# Alimentation.net
KiCad netlist of a schematic drawn in Altium Designer
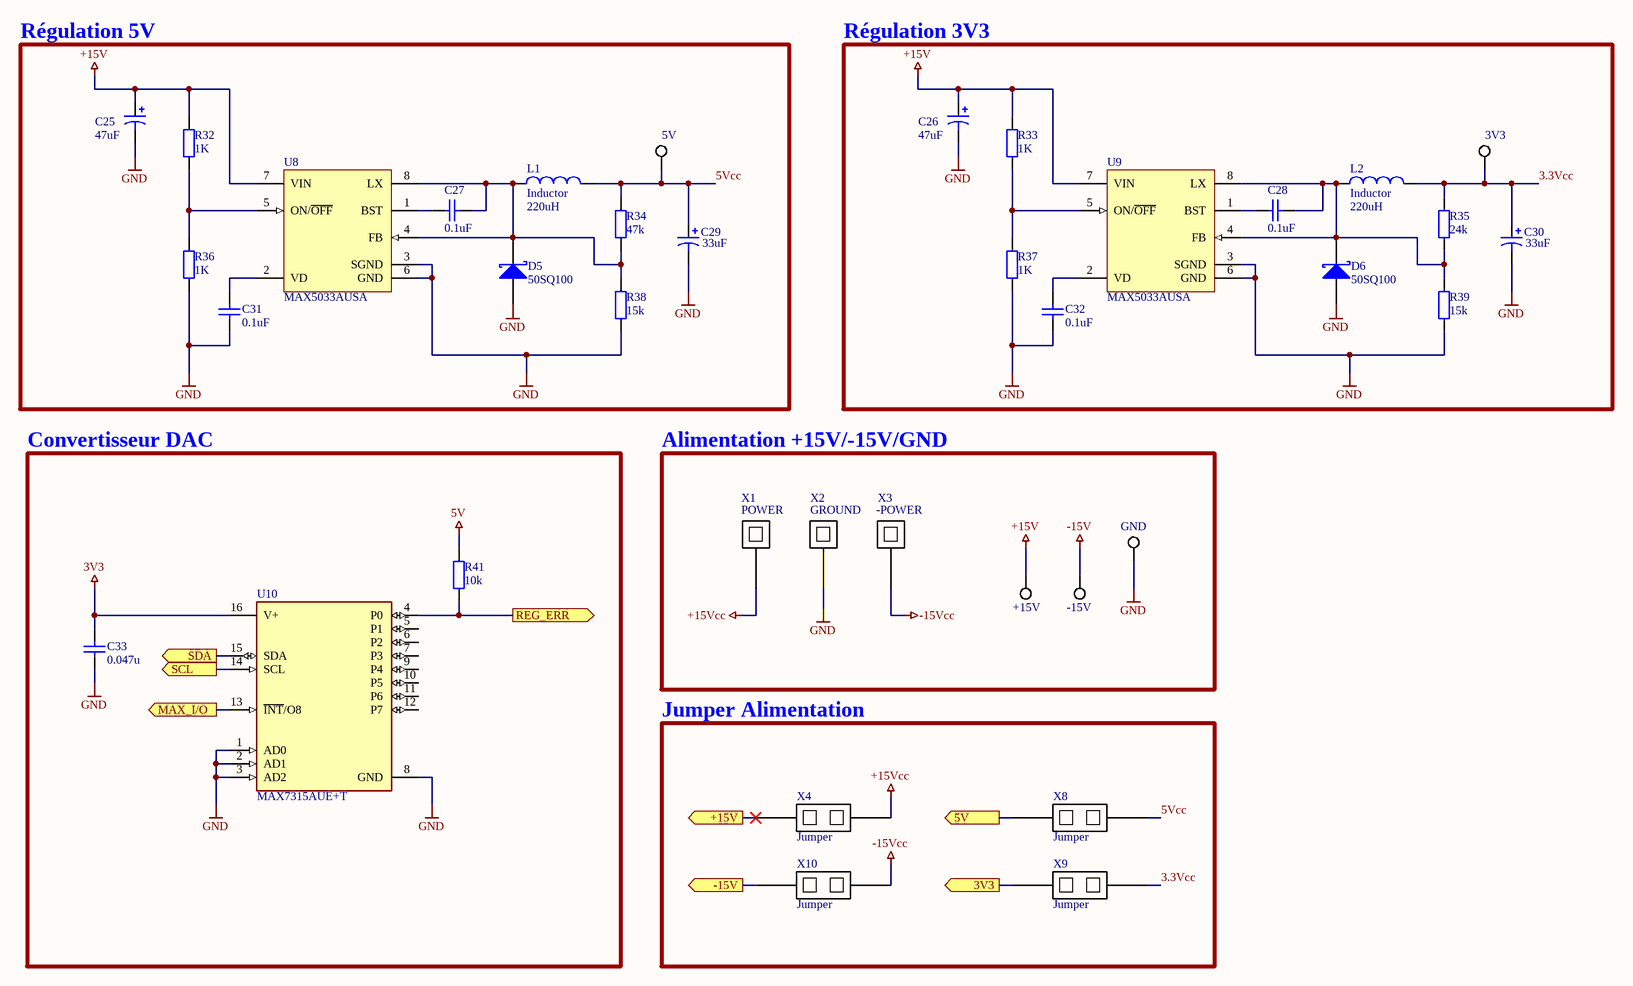
[diagram p0: Alimentation.SchDoc]

(export (version "E")
  (design (tool "Eeschema 10.0.6"))
  (components
    (comp (ref "+15V")
      (value "REGP")
      (footprint "KSTN-5019_V")
      (description "Test Point, 1 Position SMD, RoHS, Tape and Reel")
      (libsource (lib "Altium Content Vault") (part "TESTPOINT_WHITE"))
    )
    (comp (ref "-15V")
      (value "REGP")
      (footprint "KSTN-5019_V")
      (description "Test Point, 1 Position SMD, RoHS, Tape and Reel")
      (libsource (lib "Altium Content Vault") (part "TESTPOINT_WHITE"))
    )
    (comp (ref "3V3")
      (value "REGP")
      (footprint "KSTN-5019_V")
      (description "Test Point, 1 Position SMD, RoHS, Tape and Reel")
      (libsource (lib "Altium Content Vault") (part "TESTPOINT_WHITE"))
    )
    (comp (ref "5V")
      (value "REGP")
      (footprint "KSTN-5019_V")
      (description "Test Point, 1 Position SMD, RoHS, Tape and Reel")
      (libsource (lib "Altium Content Vault") (part "TESTPOINT_WHITE"))
    )
    (comp (ref "C25")
      (value "47uF")
      (footprint "C0805")
      (description "Cap Pol 47uF")
      (fields (field (name "Comment") "Cap Pol1") (field (name "PUBLISHER") "Altium Limited"))
      (libsource (lib "Miscellaneous Devices") (part "Cap Pol1"))
    )
    (comp (ref "C26")
      (value "47uF")
      (footprint "C0805")
      (description "Cap Pol 47uF")
      (fields (field (name "Comment") "Cap Pol1") (field (name "PUBLISHER") "Altium Limited"))
      (libsource (lib "Miscellaneous Devices") (part "Cap Pol1"))
    )
    (comp (ref "C27")
      (value "0.1uF")
      (footprint "C0805")
      (description "Cap 100nF")
      (fields (field (name "Comment") "Cap") (field (name "PUBLISHER") "Altium Limited"))
      (libsource (lib "Miscellaneous Devices") (part "Cap"))
    )
    (comp (ref "C28")
      (value "0.1uF")
      (footprint "C0805")
      (description "Cap 100nF")
      (fields (field (name "Comment") "Cap") (field (name "PUBLISHER") "Altium Limited"))
      (libsource (lib "Miscellaneous Devices") (part "Cap"))
    )
    (comp (ref "C29")
      (value "33uF")
      (footprint "C0805")
      (description "Cap Pol 33uF")
      (fields (field (name "Comment") "Cap Pol1") (field (name "PUBLISHER") "Altium Limited"))
      (libsource (lib "Miscellaneous Devices") (part "Cap Pol1"))
    )
    (comp (ref "C30")
      (value "33uF")
      (footprint "C0805")
      (description "Cap Pol 33uF")
      (fields (field (name "Comment") "Cap Pol1") (field (name "PUBLISHER") "Altium Limited"))
      (libsource (lib "Miscellaneous Devices") (part "Cap Pol1"))
    )
    (comp (ref "C31")
      (value "0.1uF")
      (footprint "C0805")
      (description "Cap 100nF")
      (fields (field (name "Comment") "Cap") (field (name "PUBLISHER") "Altium Limited"))
      (libsource (lib "Miscellaneous Devices") (part "Cap"))
    )
    (comp (ref "C32")
      (value "0.1uF")
      (footprint "C0805")
      (description "Cap 100nF")
      (fields (field (name "Comment") "Cap") (field (name "PUBLISHER") "Altium Limited"))
      (libsource (lib "Miscellaneous Devices") (part "Cap"))
    )
    (comp (ref "C33")
      (value "0.047u")
      (footprint "C0805")
      (description "Cap 0.047uF")
      (fields (field (name "Comment") "Cap") (field (name "PUBLISHER") "Altium Limited"))
      (libsource (lib "Miscellaneous Devices") (part "Cap"))
    )
    (comp (ref "D5")
      (value "50SQ100")
      (footprint "SODFL2513X70N")
      (description "Schottky Diode 50SQ100")
      (fields (field (name "PUBLISHER") "Altium Limited"))
      (libsource (lib "Miscellaneous Devices") (part "D Schottky"))
    )
    (comp (ref "D6")
      (value "50SQ100")
      (footprint "SODFL2513X70N")
      (description "Schottky Diode 50SQ100")
      (fields (field (name "PUBLISHER") "Altium Limited"))
      (libsource (lib "Miscellaneous Devices") (part "D Schottky"))
    )
    (comp (ref "GND")
      (value "REGP")
      (footprint "KSTN-5019_V")
      (description "Test Point, 1 Position SMD, RoHS, Tape and Reel")
      (libsource (lib "Altium Content Vault") (part "TESTPOINT_WHITE"))
    )
    (comp (ref "L1")
      (value "Inductor")
      (footprint "SDE0604A101K")
      (description "Inductor 220uH")
      (fields (field (name "ALTIUM_VALUE") "220uH") (field (name "PUBLISHER") "Altium Limited"))
      (libsource (lib "Miscellaneous Devices") (part "Inductor"))
    )
    (comp (ref "L2")
      (value "Inductor")
      (footprint "SDE0604A101K")
      (description "Inductor 220uH")
      (fields (field (name "ALTIUM_VALUE") "220uH") (field (name "PUBLISHER") "Altium Limited"))
      (libsource (lib "Miscellaneous Devices") (part "Inductor"))
    )
    (comp (ref "R32")
      (value "1K")
      (footprint "6-0805_N")
      (description "Res 1K")
      (fields (field (name "Comment") "Res2") (field (name "PUBLISHER") "Altium Limited"))
      (libsource (lib "Miscellaneous Devices") (part "Res2"))
    )
    (comp (ref "R33")
      (value "1K")
      (footprint "6-0805_N")
      (description "Res 1K")
      (fields (field (name "PUBLISHER") "Altium Limited"))
      (libsource (lib "Miscellaneous Devices") (part "Res2"))
    )
    (comp (ref "R34")
      (value "47k")
      (footprint "6-0805_N")
      (description "Resistor")
      (fields (field (name "Comment") "Res2") (field (name "PUBLISHER") "Altium Limited"))
      (libsource (lib "Miscellaneous Devices") (part "Res2"))
    )
    (comp (ref "R35")
      (value "24k")
      (footprint "6-0805_N")
      (description "Res 24K")
      (fields (field (name "Comment") "Res2") (field (name "PUBLISHER") "Altium Limited"))
      (libsource (lib "Miscellaneous Devices") (part "Res2"))
    )
    (comp (ref "R36")
      (value "1K")
      (footprint "6-0805_N")
      (description "Res 1K")
      (fields (field (name "Comment") "Res2") (field (name "PUBLISHER") "Altium Limited"))
      (libsource (lib "Miscellaneous Devices") (part "Res2"))
    )
    (comp (ref "R37")
      (value "1K")
      (footprint "6-0805_N")
      (description "Res 1K")
      (fields (field (name "PUBLISHER") "Altium Limited"))
      (libsource (lib "Miscellaneous Devices") (part "Res2"))
    )
    (comp (ref "R38")
      (value "15k")
      (footprint "6-0805_N")
      (description "Resistor")
      (fields (field (name "Comment") "Res2") (field (name "PUBLISHER") "Altium Limited"))
      (libsource (lib "Miscellaneous Devices") (part "Res2"))
    )
    (comp (ref "R39")
      (value "15k")
      (footprint "6-0805_N")
      (description "Res 15K")
      (fields (field (name "Comment") "Res2") (field (name "PUBLISHER") "Altium Limited"))
      (libsource (lib "Miscellaneous Devices") (part "Res2"))
    )
    (comp (ref "R41")
      (value "10k")
      (footprint "6-0805_N")
      (description "Res 10K")
      (fields (field (name "Comment") "Res2") (field (name "PUBLISHER") "Altium Limited"))
      (libsource (lib "Miscellaneous Devices") (part "Res2"))
    )
    (comp (ref "U8")
      (value "MAX5033AUSA")
      (footprint "S8-5_N")
      (libsource (lib "Altium Content Vault") (part "MAX-MAX5033-IL8"))
    )
    (comp (ref "U9")
      (value "MAX5033AUSA")
      (footprint "S8-5_N")
      (libsource (lib "Altium Content Vault") (part "MAX-MAX5033-IL8"))
    )
    (comp (ref "U10")
      (value "MAX7315AUE+T")
      (footprint "FP-U16-2-MFG")
      (description "IC I/O EXPANDER I2C 8B 16TSSOP")
      (libsource (lib "Altium Content Vault") (part "92d7aca338a602ce8c8694935fca5a5"))
    )
    (comp (ref "X1")
      (value "POWER")
      (footprint "PIN1")
      (description "CONN HEADER VERT 1POS")
      (libsource (lib "2019_RegThermiqueMyRio") (part "Berg"))
    )
    (comp (ref "X2")
      (value "GROUND")
      (footprint "PIN1")
      (description "CONN HEADER VERT 1POS")
      (libsource (lib "2019_RegThermiqueMyRio") (part "Berg"))
    )
    (comp (ref "X3")
      (value "-POWER")
      (footprint "PIN1")
      (description "CONN HEADER VERT 1POS")
      (libsource (lib "2019_RegThermiqueMyRio") (part "Berg"))
    )
    (comp (ref "X4")
      (value "Jumper")
      (footprint "HDR1X2")
      (description "CONN HEADER VERT 2POS 2.54MM")
      (libsource (lib "2019_RegThermiqueMyRio") (part "Jumper"))
    )
    (comp (ref "X8")
      (value "Jumper")
      (footprint "HDR1X2")
      (description "CONN HEADER VERT 2POS 2.54MM")
      (libsource (lib "2019_RegThermiqueMyRio") (part "Jumper"))
    )
    (comp (ref "X9")
      (value "Jumper")
      (footprint "HDR1X2")
      (description "CONN HEADER VERT 2POS 2.54MM")
      (libsource (lib "2019_RegThermiqueMyRio") (part "Jumper"))
    )
    (comp (ref "X10")
      (value "Jumper")
      (footprint "HDR1X2")
      (description "CONN HEADER VERT 2POS 2.54MM")
      (libsource (lib "2019_RegThermiqueMyRio") (part "Jumper"))
    )
  )
  (nets
    (net (code "1") (name "+15V") (class "Default")
      (node (ref "+15V") (pin "1") (pinfunction "1_1") (pintype "passive"))
      (node (ref "C25") (pin "1") (pinfunction "1_1") (pintype "passive"))
      (node (ref "C26") (pin "1") (pinfunction "1_1") (pintype "passive"))
      (node (ref "R32") (pin "2") (pinfunction "2_2") (pintype "passive"))
      (node (ref "R33") (pin "2") (pinfunction "2_2") (pintype "passive"))
      (node (ref "U8") (pin "7") (pinfunction "VIN_7") (pintype "passive"))
      (node (ref "U9") (pin "7") (pinfunction "VIN_7") (pintype "passive"))
      (node (ref "X4") (pin "1") (pinfunction "1_1") (pintype "passive"))
    )
    (net (code "2") (name "+15Vcc") (class "Default")
      (node (ref "X1") (pin "1") (pinfunction "1_1") (pintype "passive"))
      (node (ref "X4") (pin "2") (pinfunction "2_2") (pintype "passive"))
    )
    (net (code "3") (name "-15V") (class "Default")
      (node (ref "-15V") (pin "1") (pinfunction "1_1") (pintype "passive"))
      (node (ref "X10") (pin "1") (pinfunction "1_1") (pintype "passive"))
    )
    (net (code "4") (name "-15Vcc") (class "Default")
      (node (ref "X10") (pin "2") (pinfunction "2_2") (pintype "passive"))
      (node (ref "X3") (pin "1") (pinfunction "1_1") (pintype "passive"))
    )
    (net (code "5") (name "/3.3Vcc") (class "Default")
      (node (ref "3V3") (pin "1") (pinfunction "1_1") (pintype "passive"))
      (node (ref "C30") (pin "1") (pinfunction "1_1") (pintype "passive"))
      (node (ref "L2") (pin "2") (pinfunction "2_2") (pintype "passive"))
      (node (ref "R35") (pin "2") (pinfunction "2_2") (pintype "passive"))
      (node (ref "X9") (pin "2") (pinfunction "2_2") (pintype "passive"))
    )
    (net (code "6") (name "/5Vcc") (class "Default")
      (node (ref "5V") (pin "1") (pinfunction "1_1") (pintype "passive"))
      (node (ref "C29") (pin "1") (pinfunction "1_1") (pintype "passive"))
      (node (ref "L1") (pin "2") (pinfunction "2_2") (pintype "passive"))
      (node (ref "R34") (pin "2") (pinfunction "2_2") (pintype "passive"))
      (node (ref "X8") (pin "2") (pinfunction "2_2") (pintype "passive"))
    )
    (net (code "7") (name "/MAX_I{slash}O") (class "Default")
      (node (ref "U10") (pin "13") (pinfunction "~{INT}/O8_13") (pintype "input"))
    )
    (net (code "8") (name "/REG_ERR") (class "Default")
      (node (ref "R41") (pin "1") (pinfunction "1_1") (pintype "passive"))
      (node (ref "U10") (pin "4") (pinfunction "P0_4") (pintype "bidirectional"))
    )
    (net (code "9") (name "/SCL") (class "Default")
      (node (ref "U10") (pin "14") (pinfunction "SCL_14") (pintype "input"))
    )
    (net (code "10") (name "/SDA") (class "Default")
      (node (ref "U10") (pin "15") (pinfunction "SDA_15") (pintype "bidirectional"))
    )
    (net (code "11") (name "3V3") (class "Default")
      (node (ref "C33") (pin "2") (pinfunction "2_2") (pintype "passive"))
      (node (ref "U10") (pin "16") (pinfunction "V+_16") (pintype "power_in"))
      (node (ref "X9") (pin "1") (pinfunction "1_1") (pintype "passive"))
    )
    (net (code "12") (name "5V") (class "Default")
      (node (ref "R41") (pin "2") (pinfunction "2_2") (pintype "passive"))
      (node (ref "X8") (pin "1") (pinfunction "1_1") (pintype "passive"))
    )
    (net (code "13") (name "GND") (class "Default")
      (node (ref "C25") (pin "2") (pinfunction "2_2") (pintype "passive"))
      (node (ref "C26") (pin "2") (pinfunction "2_2") (pintype "passive"))
      (node (ref "C29") (pin "2") (pinfunction "2_2") (pintype "passive"))
      (node (ref "C30") (pin "2") (pinfunction "2_2") (pintype "passive"))
      (node (ref "C31") (pin "2") (pinfunction "2_2") (pintype "passive"))
      (node (ref "C32") (pin "2") (pinfunction "2_2") (pintype "passive"))
      (node (ref "C33") (pin "1") (pinfunction "1_1") (pintype "passive"))
      (node (ref "D5") (pin "1") (pinfunction "A_1") (pintype "passive"))
      (node (ref "D6") (pin "1") (pinfunction "A_1") (pintype "passive"))
      (node (ref "GND") (pin "1") (pinfunction "1_1") (pintype "passive"))
      (node (ref "R36") (pin "1") (pinfunction "1_1") (pintype "passive"))
      (node (ref "R37") (pin "1") (pinfunction "1_1") (pintype "passive"))
      (node (ref "R38") (pin "1") (pinfunction "1_1") (pintype "passive"))
      (node (ref "R39") (pin "1") (pinfunction "1_1") (pintype "passive"))
      (node (ref "U10") (pin "1") (pinfunction "AD0_1") (pintype "input"))
      (node (ref "U10") (pin "2") (pinfunction "AD1_2") (pintype "input"))
      (node (ref "U10") (pin "3") (pinfunction "AD2_3") (pintype "input"))
      (node (ref "U10") (pin "8") (pinfunction "GND_8") (pintype "power_in"))
      (node (ref "U8") (pin "3") (pinfunction "SGND_3") (pintype "power_in"))
      (node (ref "U8") (pin "6") (pinfunction "GND_6") (pintype "power_in"))
      (node (ref "U9") (pin "3") (pinfunction "SGND_3") (pintype "power_in"))
      (node (ref "U9") (pin "6") (pinfunction "GND_6") (pintype "power_in"))
      (node (ref "X2") (pin "1") (pinfunction "1_1") (pintype "passive"))
    )
    (net (code "14") (name "Net-(D5-K)") (class "Default")
      (node (ref "C27") (pin "2") (pinfunction "2_2") (pintype "passive"))
      (node (ref "D5") (pin "2") (pinfunction "K_2") (pintype "passive"))
      (node (ref "L1") (pin "1") (pinfunction "1_1") (pintype "passive"))
      (node (ref "R34") (pin "1") (pinfunction "1_1") (pintype "passive"))
      (node (ref "R38") (pin "2") (pinfunction "2_2") (pintype "passive"))
      (node (ref "U8") (pin "4") (pinfunction "FB_4") (pintype "input"))
      (node (ref "U8") (pin "8") (pinfunction "LX_8") (pintype "passive"))
    )
    (net (code "15") (name "Net-(D6-K)") (class "Default")
      (node (ref "C28") (pin "2") (pinfunction "2_2") (pintype "passive"))
      (node (ref "D6") (pin "2") (pinfunction "K_2") (pintype "passive"))
      (node (ref "L2") (pin "1") (pinfunction "1_1") (pintype "passive"))
      (node (ref "R35") (pin "1") (pinfunction "1_1") (pintype "passive"))
      (node (ref "R39") (pin "2") (pinfunction "2_2") (pintype "passive"))
      (node (ref "U9") (pin "4") (pinfunction "FB_4") (pintype "input"))
      (node (ref "U9") (pin "8") (pinfunction "LX_8") (pintype "passive"))
    )
    (net (code "16") (name "Net-(U8-BST)") (class "Default")
      (node (ref "C27") (pin "1") (pinfunction "1_1") (pintype "passive"))
      (node (ref "U8") (pin "1") (pinfunction "BST_1") (pintype "passive"))
    )
    (net (code "17") (name "Net-(U8-ON{slash}~{OFF})") (class "Default")
      (node (ref "R32") (pin "1") (pinfunction "1_1") (pintype "passive"))
      (node (ref "R36") (pin "2") (pinfunction "2_2") (pintype "passive"))
      (node (ref "U8") (pin "5") (pinfunction "ON/~{OFF}_5") (pintype "input"))
    )
    (net (code "18") (name "Net-(U8-VD)") (class "Default")
      (node (ref "C31") (pin "1") (pinfunction "1_1") (pintype "passive"))
      (node (ref "U8") (pin "2") (pinfunction "VD_2") (pintype "power_in"))
    )
    (net (code "19") (name "Net-(U9-BST)") (class "Default")
      (node (ref "C28") (pin "1") (pinfunction "1_1") (pintype "passive"))
      (node (ref "U9") (pin "1") (pinfunction "BST_1") (pintype "passive"))
    )
    (net (code "20") (name "Net-(U9-ON{slash}~{OFF})") (class "Default")
      (node (ref "R33") (pin "1") (pinfunction "1_1") (pintype "passive"))
      (node (ref "R37") (pin "2") (pinfunction "2_2") (pintype "passive"))
      (node (ref "U9") (pin "5") (pinfunction "ON/~{OFF}_5") (pintype "input"))
    )
    (net (code "21") (name "Net-(U9-VD)") (class "Default")
      (node (ref "C32") (pin "1") (pinfunction "1_1") (pintype "passive"))
      (node (ref "U9") (pin "2") (pinfunction "VD_2") (pintype "power_in"))
    )
    (net (code "22") (name "unconnected-(U10-P1-Pad5)") (class "Default")
      (node (ref "U10") (pin "5") (pinfunction "P1_5") (pintype "bidirectional"))
    )
    (net (code "23") (name "unconnected-(U10-P2-Pad6)") (class "Default")
      (node (ref "U10") (pin "6") (pinfunction "P2_6") (pintype "bidirectional"))
    )
    (net (code "24") (name "unconnected-(U10-P3-Pad7)") (class "Default")
      (node (ref "U10") (pin "7") (pinfunction "P3_7") (pintype "bidirectional"))
    )
    (net (code "25") (name "unconnected-(U10-P4-Pad9)") (class "Default")
      (node (ref "U10") (pin "9") (pinfunction "P4_9") (pintype "bidirectional"))
    )
    (net (code "26") (name "unconnected-(U10-P5-Pad10)") (class "Default")
      (node (ref "U10") (pin "10") (pinfunction "P5_10") (pintype "bidirectional"))
    )
    (net (code "27") (name "unconnected-(U10-P6-Pad11)") (class "Default")
      (node (ref "U10") (pin "11") (pinfunction "P6_11") (pintype "bidirectional"))
    )
    (net (code "28") (name "unconnected-(U10-P7-Pad12)") (class "Default")
      (node (ref "U10") (pin "12") (pinfunction "P7_12") (pintype "bidirectional"))
    )
  )
)
